# ALU_ONE.net
KiCad netlist of a schematic drawn in Altium Designer
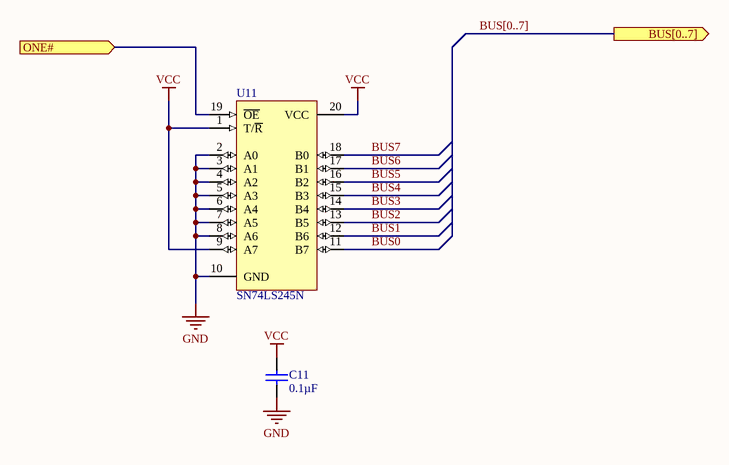
[diagram p0: ALU_ONE.SchDoc]

(export (version "E")
  (design (tool "Eeschema 10.0.6"))
  (components
    (comp (ref "C11")
      (value "K104K15X7RF5TL2")
      (footprint "VISH-K104K15X7RF5TL2")
      (description "Ceramic Capacitor, 100 nF, +/- 10%, 50 V, -55 to 125 degC, 2-Pin THD, RoHS, Tape and Reel")
      (fields
        (field (name "MANUFACTURER") "Vishay")
        (field (name "TOLERANCE") "±10%")
        (field (name "CAPACITANCE") "0.1µF")
      )
      (libsource (lib "Altium Content Vault") (part "CAP-NP-2"))
    )
    (comp (ref "U11")
      (value "SN74LS245N")
      (footprint "N020")
      (description "Octal Bus Transceiver with 3-State Outputs")
      (fields (field (name "PUBLISHER") "Altium Limited"))
      (libsource (lib "TI Interface 8-Bit Line Transceiver") (part "SN74LS245N"))
    )
  )
  (nets
    (net (code "1") (name "/BUS0") (class "Default")
      (node (ref "U11") (pin "11") (pinfunction "B7_11") (pintype "bidirectional"))
    )
    (net (code "2") (name "/BUS1") (class "Default")
      (node (ref "U11") (pin "12") (pinfunction "B6_12") (pintype "bidirectional"))
    )
    (net (code "3") (name "/BUS2") (class "Default")
      (node (ref "U11") (pin "13") (pinfunction "B5_13") (pintype "bidirectional"))
    )
    (net (code "4") (name "/BUS3") (class "Default")
      (node (ref "U11") (pin "14") (pinfunction "B4_14") (pintype "bidirectional"))
    )
    (net (code "5") (name "/BUS4") (class "Default")
      (node (ref "U11") (pin "15") (pinfunction "B3_15") (pintype "bidirectional"))
    )
    (net (code "6") (name "/BUS5") (class "Default")
      (node (ref "U11") (pin "16") (pinfunction "B2_16") (pintype "bidirectional"))
    )
    (net (code "7") (name "/BUS6") (class "Default")
      (node (ref "U11") (pin "17") (pinfunction "B1_17") (pintype "bidirectional"))
    )
    (net (code "8") (name "/BUS7") (class "Default")
      (node (ref "U11") (pin "18") (pinfunction "B0_18") (pintype "bidirectional"))
    )
    (net (code "10") (name "/ONE#") (class "Default")
      (node (ref "U11") (pin "19") (pinfunction "~{OE}_19") (pintype "input"))
    )
    (net (code "11") (name "GND") (class "Default")
      (node (ref "C11") (pin "2") (pinfunction "2_2") (pintype "passive"))
      (node (ref "U11") (pin "10") (pinfunction "GND_10") (pintype "power_in"))
      (node (ref "U11") (pin "2") (pinfunction "A0_2") (pintype "bidirectional"))
      (node (ref "U11") (pin "3") (pinfunction "A1_3") (pintype "bidirectional"))
      (node (ref "U11") (pin "4") (pinfunction "A2_4") (pintype "bidirectional"))
      (node (ref "U11") (pin "5") (pinfunction "A3_5") (pintype "bidirectional"))
      (node (ref "U11") (pin "6") (pinfunction "A4_6") (pintype "bidirectional"))
      (node (ref "U11") (pin "7") (pinfunction "A5_7") (pintype "bidirectional"))
      (node (ref "U11") (pin "8") (pinfunction "A6_8") (pintype "bidirectional"))
    )
    (net (code "12") (name "VCC") (class "Default")
      (node (ref "C11") (pin "1") (pinfunction "1_1") (pintype "passive"))
      (node (ref "U11") (pin "1") (pinfunction "T/~{R}_1") (pintype "input"))
      (node (ref "U11") (pin "20") (pinfunction "VCC_20") (pintype "power_in"))
      (node (ref "U11") (pin "9") (pinfunction "A7_9") (pintype "bidirectional"))
    )
  )
)
